# 20140816_PIC16F1827_BASE.net
KiCad netlist of a schematic drawn in EAGLE
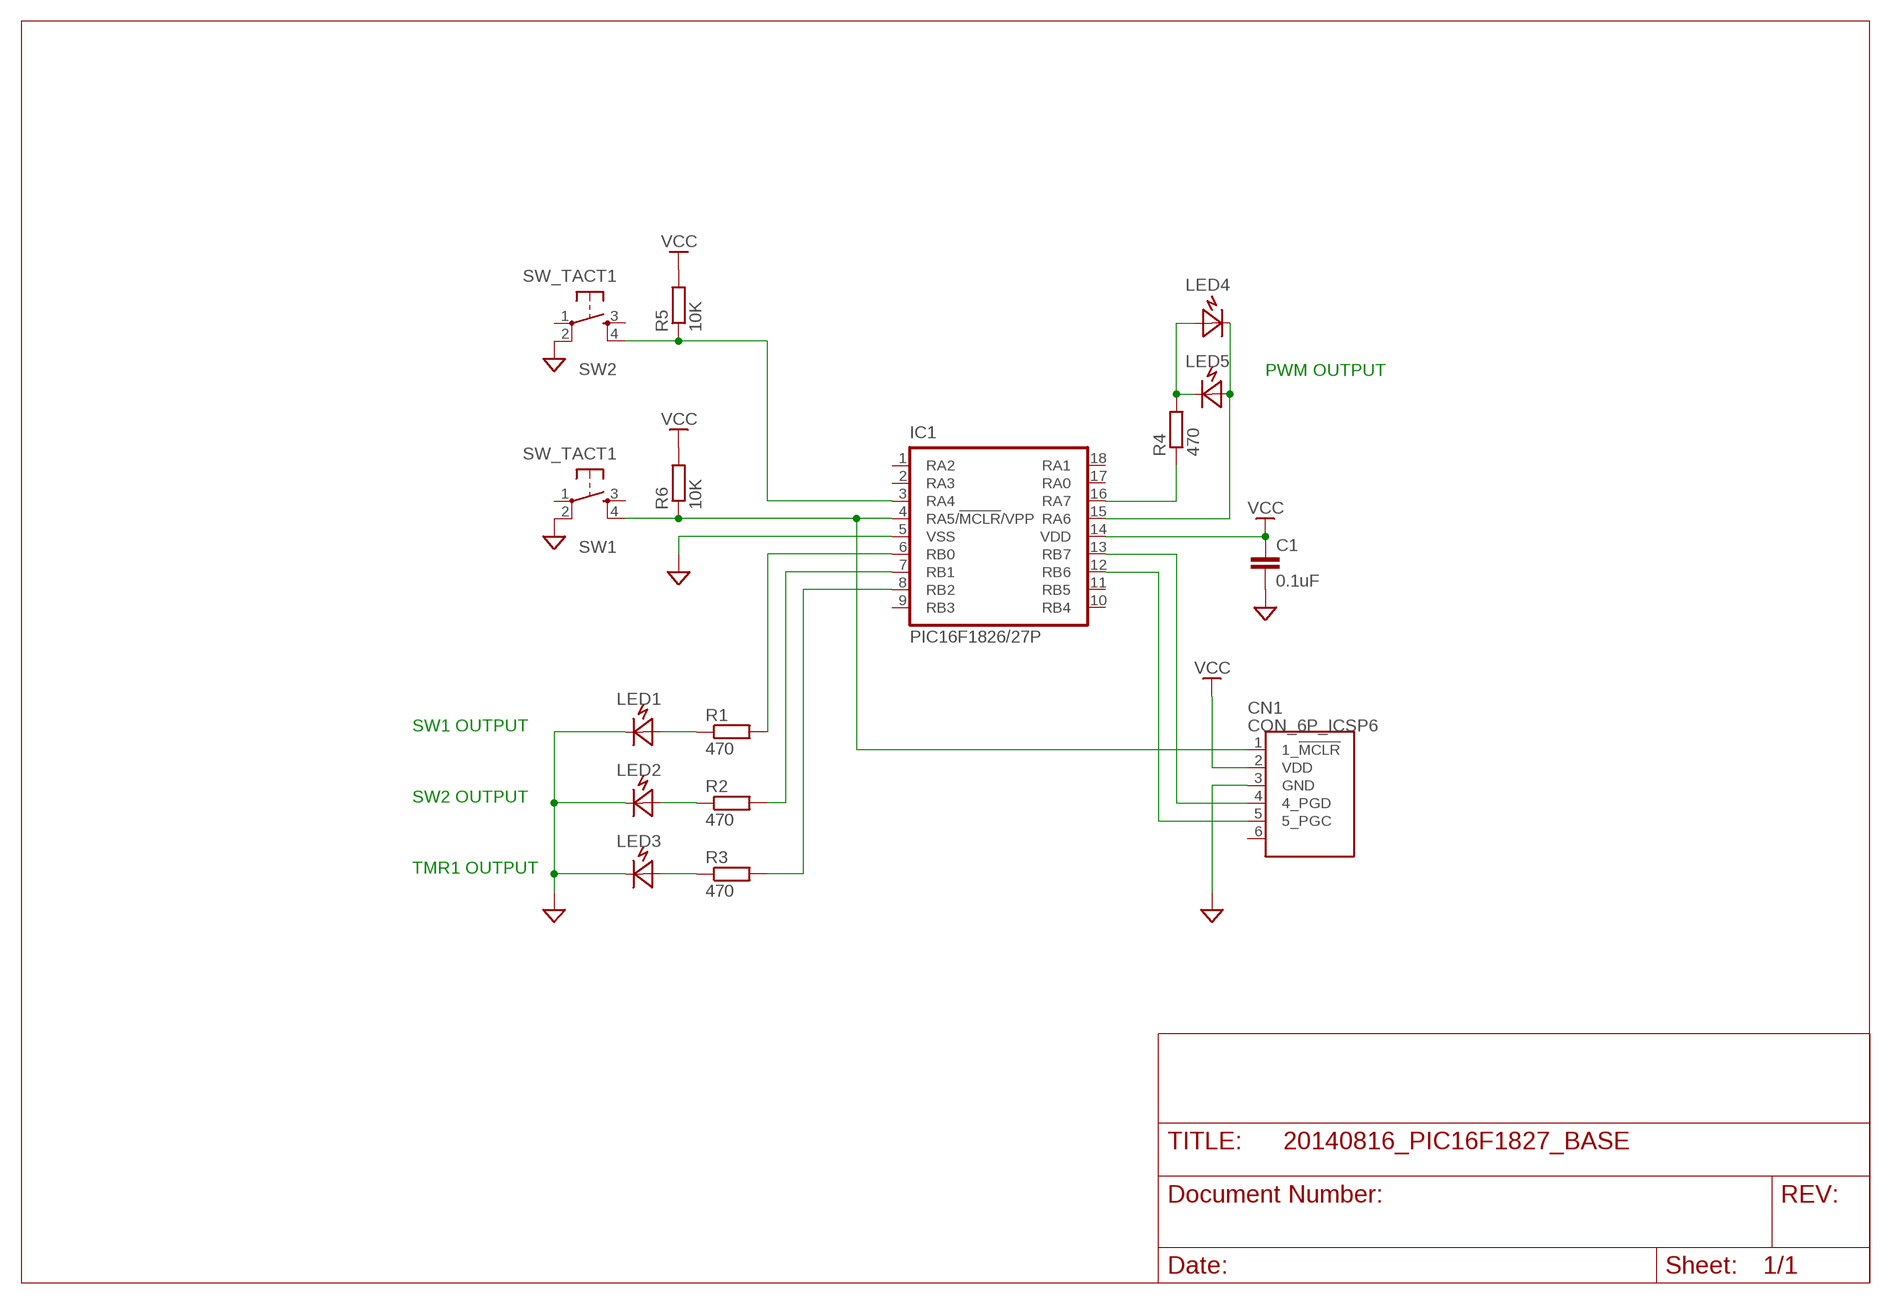
[diagram p0: schematic, sheet 1]

(export (version "E")
  (design (tool "Eeschema 10.0.6"))
  (components
    (comp (ref "C1")
      (value "0.1uF")
      (footprint "eagle-import:C025-025X050-A")
      (libsource (lib "eagle-import") (part "C-EU2025-025X050A"))
    )
    (comp (ref "CN1")
      (value "CON_6P_ICSP6")
      (footprint "eagle-import:CON_HRS_DIP_6")
      (libsource (lib "eagle-import") (part "CON_6P_ICSP6"))
    )
    (comp (ref "IC1")
      (value "PIC16F1826/27P")
      (footprint "eagle-import:DIL18")
      (libsource (lib "eagle-import") (part "PIC16F1826/27P"))
    )
    (comp (ref "LED1")
      (value "LED\"\"")
      (footprint "eagle-import:LED_3MM_VIRT_2")
      (libsource (lib "eagle-import") (part "LED{dblquote}{dblquote}"))
    )
    (comp (ref "LED2")
      (value "LED\"\"")
      (footprint "eagle-import:LED_3MM_VIRT_2")
      (libsource (lib "eagle-import") (part "LED{dblquote}{dblquote}"))
    )
    (comp (ref "LED3")
      (value "LED\"\"")
      (footprint "eagle-import:LED_3MM_VIRT_2")
      (libsource (lib "eagle-import") (part "LED{dblquote}{dblquote}"))
    )
    (comp (ref "LED4")
      (value "LED\"\"")
      (footprint "eagle-import:LED_3MM_VIRT_2")
      (libsource (lib "eagle-import") (part "LED{dblquote}{dblquote}"))
    )
    (comp (ref "LED5")
      (value "LED\"\"")
      (footprint "eagle-import:LED_3MM_VIRT_2")
      (libsource (lib "eagle-import") (part "LED{dblquote}{dblquote}"))
    )
    (comp (ref "R1")
      (value "470")
      (footprint "eagle-import:0204_5-A")
      (libsource (lib "eagle-import") (part "R-EU20204/5A"))
    )
    (comp (ref "R2")
      (value "470")
      (footprint "eagle-import:0204_5-A")
      (libsource (lib "eagle-import") (part "R-EU20204/5A"))
    )
    (comp (ref "R3")
      (value "470")
      (footprint "eagle-import:0204_5-A")
      (libsource (lib "eagle-import") (part "R-EU20204/5A"))
    )
    (comp (ref "R4")
      (value "470")
      (footprint "eagle-import:0204_5-A")
      (libsource (lib "eagle-import") (part "R-EU20204/5A"))
    )
    (comp (ref "R5")
      (value "10K")
      (footprint "eagle-import:0204_5-A")
      (libsource (lib "eagle-import") (part "R-EU20204/5A"))
    )
    (comp (ref "R6")
      (value "10K")
      (footprint "eagle-import:0204_5-A")
      (libsource (lib "eagle-import") (part "R-EU20204/5A"))
    )
    (comp (ref "SW1")
      (value "SW_TACT1")
      (footprint "eagle-import:SW_TACT")
      (libsource (lib "eagle-import") (part "SW_TACT1"))
    )
    (comp (ref "SW2")
      (value "SW_TACT1")
      (footprint "eagle-import:SW_TACT")
      (libsource (lib "eagle-import") (part "SW_TACT1"))
    )
  )
  (nets
    (net (code "1") (name "GND") (class "Default")
      (node (ref "C1") (pin "2") (pinfunction "2_2") (pintype "passive"))
      (node (ref "CN1") (pin "3") (pinfunction "GND_3") (pintype "passive"))
      (node (ref "IC1") (pin "5") (pinfunction "VSS_5") (pintype "power_in"))
      (node (ref "LED1") (pin "K") (pinfunction "K_K") (pintype "passive"))
      (node (ref "LED2") (pin "K") (pinfunction "K_K") (pintype "passive"))
      (node (ref "LED3") (pin "K") (pinfunction "K_K") (pintype "passive"))
      (node (ref "SW1") (pin "2") (pinfunction "P1_2") (pintype "passive"))
      (node (ref "SW2") (pin "2") (pinfunction "P1_2") (pintype "passive"))
    )
    (net (code "2") (name "Net-(CN1-1_~{MCLR})") (class "Default")
      (node (ref "CN1") (pin "1") (pinfunction "1_~{MCLR}_1") (pintype "passive"))
      (node (ref "IC1") (pin "4") (pinfunction "RA5/~{MCLR}/VPP_4") (pintype "bidirectional"))
      (node (ref "R6") (pin "1") (pinfunction "1_1") (pintype "passive"))
      (node (ref "SW1") (pin "4") (pinfunction "S1_4") (pintype "passive"))
    )
    (net (code "3") (name "Net-(CN1-4_PGD)") (class "Default")
      (node (ref "CN1") (pin "4") (pinfunction "4_PGD_4") (pintype "passive"))
      (node (ref "IC1") (pin "13") (pinfunction "RB7_13") (pintype "bidirectional"))
    )
    (net (code "4") (name "Net-(CN1-5_PGC)") (class "Default")
      (node (ref "CN1") (pin "5") (pinfunction "5_PGC_5") (pintype "passive"))
      (node (ref "IC1") (pin "12") (pinfunction "RB6_12") (pintype "bidirectional"))
    )
    (net (code "5") (name "Net-(IC1-RA4)") (class "Default")
      (node (ref "IC1") (pin "3") (pinfunction "RA4_3") (pintype "bidirectional"))
      (node (ref "R5") (pin "1") (pinfunction "1_1") (pintype "passive"))
      (node (ref "SW2") (pin "4") (pinfunction "S1_4") (pintype "passive"))
    )
    (net (code "6") (name "Net-(IC1-RA6)") (class "Default")
      (node (ref "IC1") (pin "15") (pinfunction "RA6_15") (pintype "bidirectional"))
      (node (ref "LED4") (pin "K") (pinfunction "K_K") (pintype "passive"))
      (node (ref "LED5") (pin "A") (pinfunction "A_A") (pintype "passive"))
    )
    (net (code "7") (name "Net-(IC1-RA7)") (class "Default")
      (node (ref "IC1") (pin "16") (pinfunction "RA7_16") (pintype "bidirectional"))
      (node (ref "R4") (pin "1") (pinfunction "1_1") (pintype "passive"))
    )
    (net (code "8") (name "Net-(IC1-RB0)") (class "Default")
      (node (ref "IC1") (pin "6") (pinfunction "RB0_6") (pintype "bidirectional"))
      (node (ref "R1") (pin "2") (pinfunction "2_2") (pintype "passive"))
    )
    (net (code "9") (name "Net-(IC1-RB1)") (class "Default")
      (node (ref "IC1") (pin "7") (pinfunction "RB1_7") (pintype "bidirectional"))
      (node (ref "R2") (pin "2") (pinfunction "2_2") (pintype "passive"))
    )
    (net (code "10") (name "Net-(IC1-RB2)") (class "Default")
      (node (ref "IC1") (pin "8") (pinfunction "RB2_8") (pintype "bidirectional"))
      (node (ref "R3") (pin "2") (pinfunction "2_2") (pintype "passive"))
    )
    (net (code "11") (name "Net-(LED1-PadA)") (class "Default")
      (node (ref "LED1") (pin "A") (pinfunction "A_A") (pintype "passive"))
      (node (ref "R1") (pin "1") (pinfunction "1_1") (pintype "passive"))
    )
    (net (code "12") (name "Net-(LED2-PadA)") (class "Default")
      (node (ref "LED2") (pin "A") (pinfunction "A_A") (pintype "passive"))
      (node (ref "R2") (pin "1") (pinfunction "1_1") (pintype "passive"))
    )
    (net (code "13") (name "Net-(LED3-PadA)") (class "Default")
      (node (ref "LED3") (pin "A") (pinfunction "A_A") (pintype "passive"))
      (node (ref "R3") (pin "1") (pinfunction "1_1") (pintype "passive"))
    )
    (net (code "14") (name "Net-(LED4-PadA)") (class "Default")
      (node (ref "LED4") (pin "A") (pinfunction "A_A") (pintype "passive"))
      (node (ref "LED5") (pin "K") (pinfunction "K_K") (pintype "passive"))
      (node (ref "R4") (pin "2") (pinfunction "2_2") (pintype "passive"))
    )
    (net (code "15") (name "VCC") (class "Default")
      (node (ref "C1") (pin "1") (pinfunction "1_1") (pintype "passive"))
      (node (ref "CN1") (pin "2") (pinfunction "VDD_2") (pintype "passive"))
      (node (ref "IC1") (pin "14") (pinfunction "VDD_14") (pintype "power_in"))
      (node (ref "R5") (pin "2") (pinfunction "2_2") (pintype "passive"))
      (node (ref "R6") (pin "2") (pinfunction "2_2") (pintype "passive"))
    )
    (net (code "16") (name "unconnected-(CN1-Pad6)") (class "Default")
      (node (ref "CN1") (pin "6") (pinfunction "6_6") (pintype "passive"))
    )
    (net (code "17") (name "unconnected-(IC1-RA0-Pad17)") (class "Default")
      (node (ref "IC1") (pin "17") (pinfunction "RA0_17") (pintype "bidirectional"))
    )
    (net (code "18") (name "unconnected-(IC1-RA1-Pad18)") (class "Default")
      (node (ref "IC1") (pin "18") (pinfunction "RA1_18") (pintype "bidirectional"))
    )
    (net (code "19") (name "unconnected-(IC1-RA2-Pad1)") (class "Default")
      (node (ref "IC1") (pin "1") (pinfunction "RA2_1") (pintype "bidirectional"))
    )
    (net (code "20") (name "unconnected-(IC1-RA3-Pad2)") (class "Default")
      (node (ref "IC1") (pin "2") (pinfunction "RA3_2") (pintype "bidirectional"))
    )
    (net (code "21") (name "unconnected-(IC1-RB3-Pad9)") (class "Default")
      (node (ref "IC1") (pin "9") (pinfunction "RB3_9") (pintype "bidirectional"))
    )
    (net (code "22") (name "unconnected-(IC1-RB4-Pad10)") (class "Default")
      (node (ref "IC1") (pin "10") (pinfunction "RB4_10") (pintype "bidirectional"))
    )
    (net (code "23") (name "unconnected-(IC1-RB5-Pad11)") (class "Default")
      (node (ref "IC1") (pin "11") (pinfunction "RB5_11") (pintype "bidirectional"))
    )
    (net (code "24") (name "unconnected-(SW1-P-Pad1)") (class "Default")
      (node (ref "SW1") (pin "1") (pinfunction "P_1") (pintype "passive"))
    )
    (net (code "25") (name "unconnected-(SW1-S-Pad3)") (class "Default")
      (node (ref "SW1") (pin "3") (pinfunction "S_3") (pintype "passive"))
    )
    (net (code "26") (name "unconnected-(SW2-P-Pad1)") (class "Default")
      (node (ref "SW2") (pin "1") (pinfunction "P_1") (pintype "passive"))
    )
    (net (code "27") (name "unconnected-(SW2-S-Pad3)") (class "Default")
      (node (ref "SW2") (pin "3") (pinfunction "S_3") (pintype "passive"))
    )
  )
)
